# P-MT3620RDB-1-7_Dev.net
KiCad netlist of a schematic drawn in Altium Designer
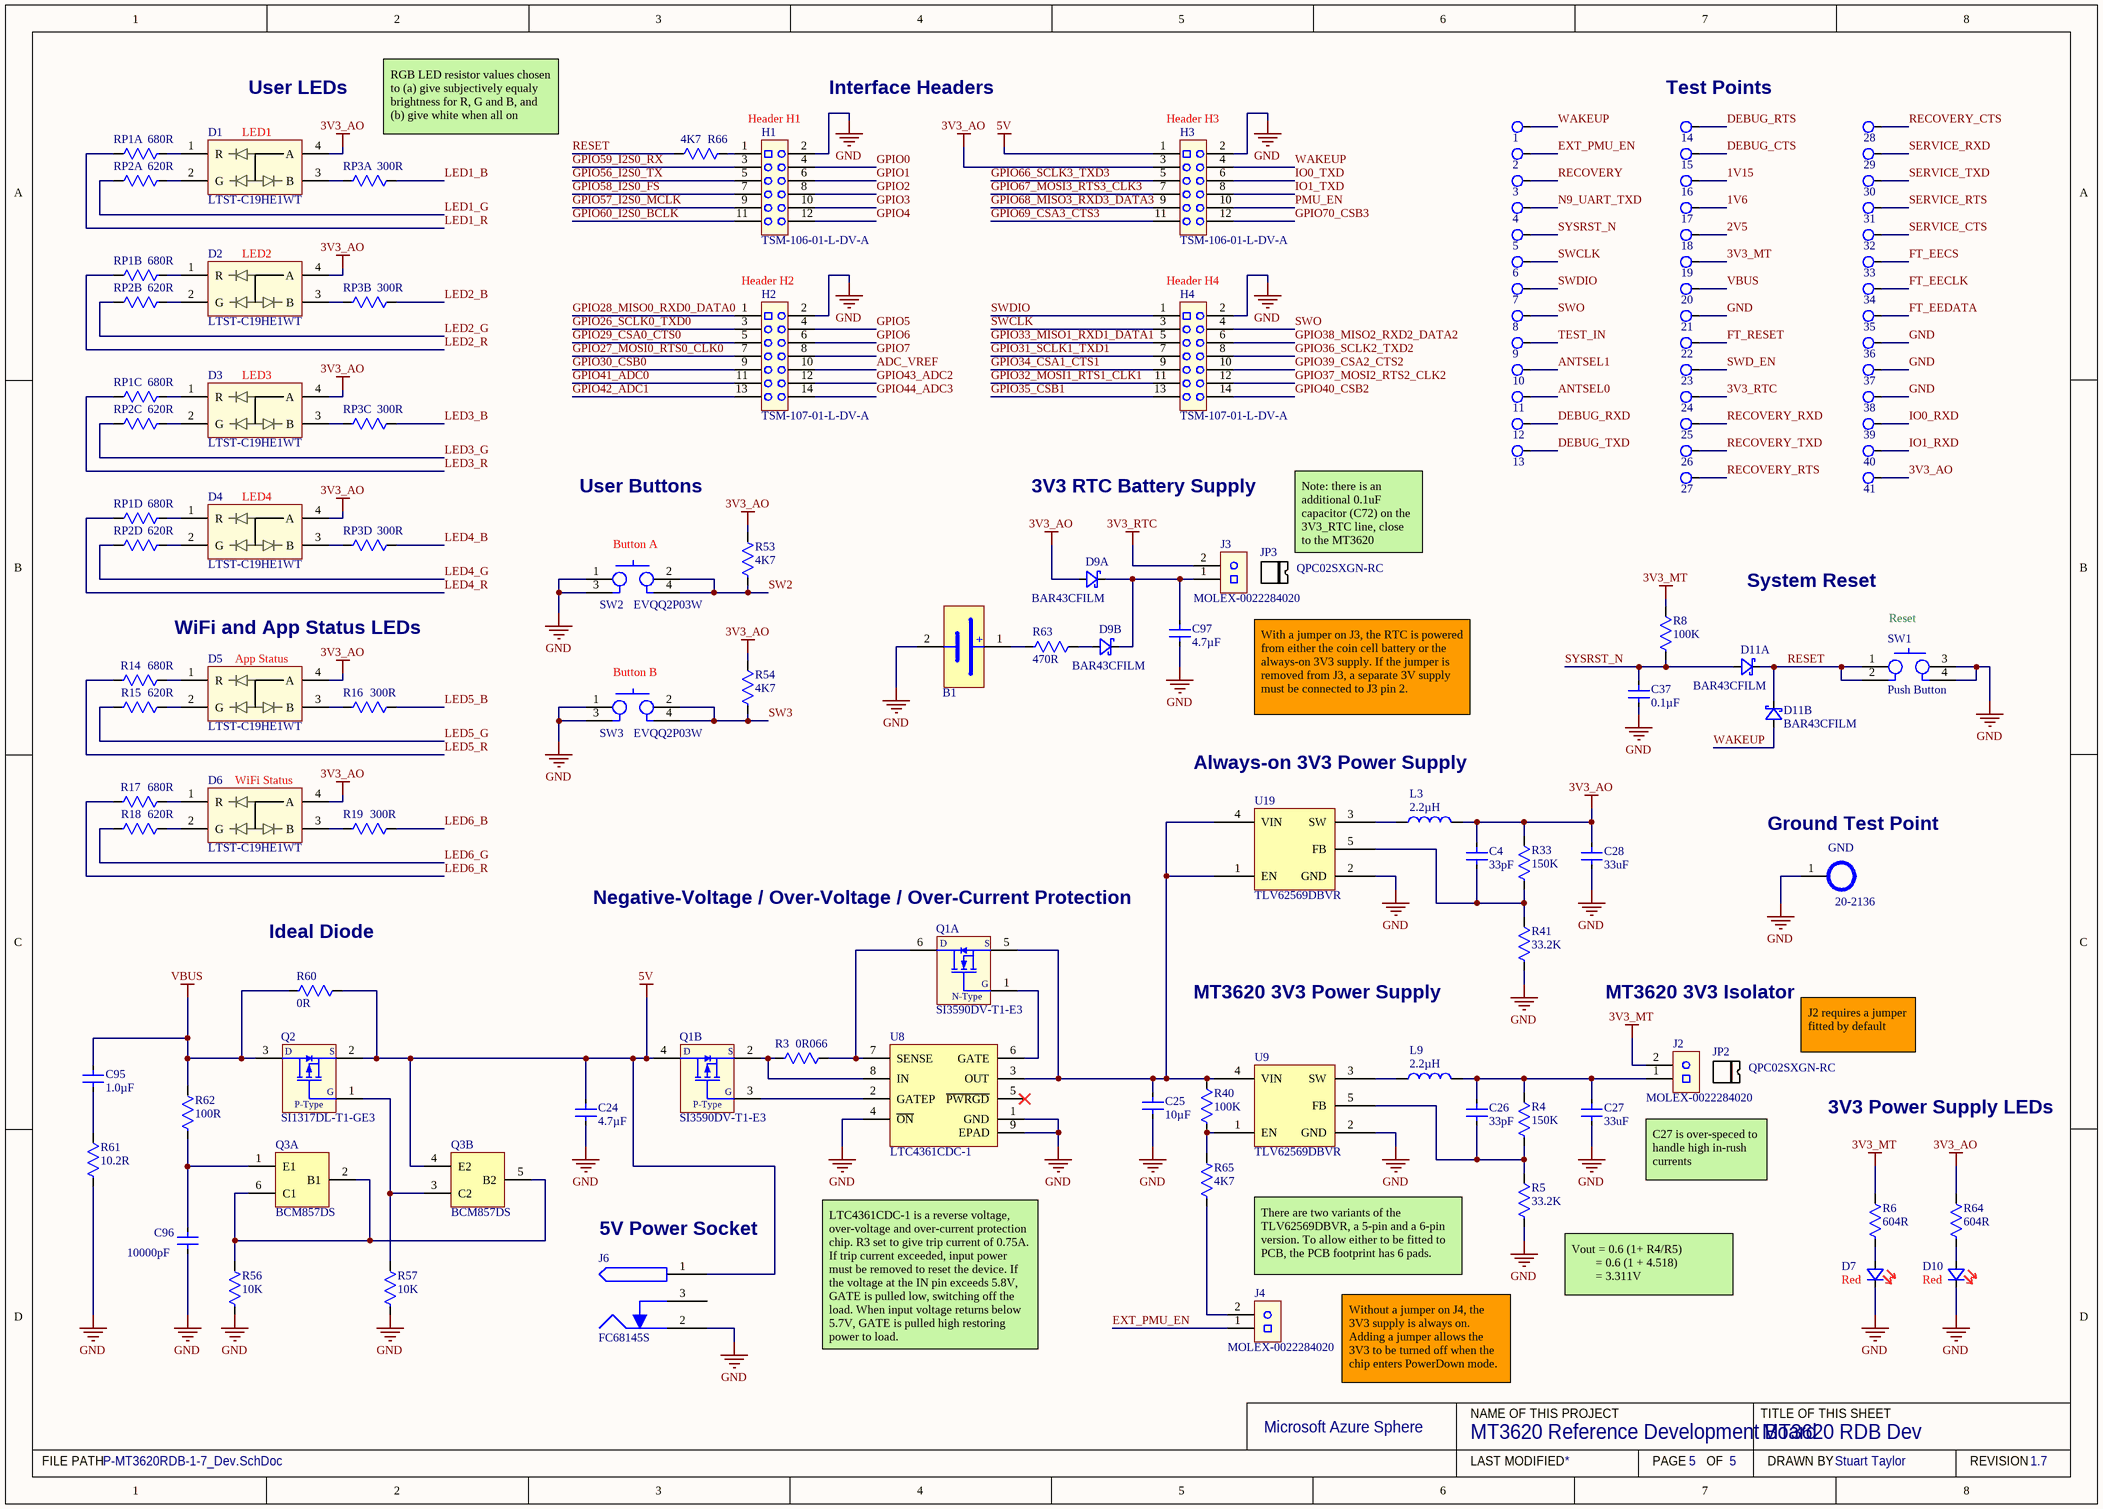
[diagram p0: P-MT3620RDB-1-7_Dev.SchDoc]

(export (version "E")
  (design (tool "Eeschema 10.0.6"))
  (components
    (comp (ref "1")
      (value "TestPoint")
      (footprint "Pad1.27mm")
      (description "Test Point")
      (libsource (lib "generic") (part "TestPoint"))
    )
    (comp (ref "2")
      (value "TestPoint")
      (footprint "Pad1.27mm")
      (description "Test Point")
      (libsource (lib "generic") (part "TestPoint"))
    )
    (comp (ref "3")
      (value "TestPoint")
      (footprint "Pad1.27mm")
      (description "Test Point")
      (libsource (lib "generic") (part "TestPoint"))
    )
    (comp (ref "4")
      (value "TestPoint")
      (footprint "Pad1.27mm")
      (description "Test Point")
      (libsource (lib "generic") (part "TestPoint"))
    )
    (comp (ref "5")
      (value "TestPoint")
      (footprint "Pad1.27mm")
      (description "Test Point")
      (libsource (lib "generic") (part "TestPoint"))
    )
    (comp (ref "6")
      (value "TestPoint")
      (footprint "Pad1.27mm")
      (description "Test Point")
      (libsource (lib "generic") (part "TestPoint"))
    )
    (comp (ref "7")
      (value "TestPoint")
      (footprint "Pad1.27mm")
      (description "Test Point")
      (libsource (lib "generic") (part "TestPoint"))
    )
    (comp (ref "8")
      (value "TestPoint")
      (footprint "Pad1.27mm")
      (description "Test Point")
      (libsource (lib "generic") (part "TestPoint"))
    )
    (comp (ref "9")
      (value "TestPoint")
      (footprint "Pad1.27mm")
      (description "Test Point")
      (libsource (lib "generic") (part "TestPoint"))
    )
    (comp (ref "10")
      (value "TestPoint")
      (footprint "Pad1.27mm")
      (description "Test Point")
      (libsource (lib "generic") (part "TestPoint"))
    )
    (comp (ref "11")
      (value "TestPoint")
      (footprint "Pad1.27mm")
      (description "Test Point")
      (libsource (lib "generic") (part "TestPoint"))
    )
    (comp (ref "12")
      (value "TestPoint")
      (footprint "Pad1.27mm")
      (description "Test Point")
      (libsource (lib "generic") (part "TestPoint"))
    )
    (comp (ref "13")
      (value "TestPoint")
      (footprint "Pad1.27mm")
      (description "Test Point")
      (libsource (lib "generic") (part "TestPoint"))
    )
    (comp (ref "14")
      (value "TestPoint")
      (footprint "Pad1.27mm")
      (description "Test Point")
      (libsource (lib "generic") (part "TestPoint"))
    )
    (comp (ref "15")
      (value "TestPoint")
      (footprint "Pad1.27mm")
      (description "Test Point")
      (libsource (lib "generic") (part "TestPoint"))
    )
    (comp (ref "16")
      (value "TestPoint")
      (footprint "Pad1.27mm")
      (description "Test Point")
      (libsource (lib "generic") (part "TestPoint"))
    )
    (comp (ref "17")
      (value "TestPoint")
      (footprint "Pad1.27mm")
      (description "Test Point")
      (libsource (lib "generic") (part "TestPoint"))
    )
    (comp (ref "18")
      (value "TestPoint")
      (footprint "Pad1.27mm")
      (description "Test Point")
      (libsource (lib "generic") (part "TestPoint"))
    )
    (comp (ref "19")
      (value "TestPoint")
      (footprint "Pad1.27mm")
      (description "Test Point")
      (libsource (lib "generic") (part "TestPoint"))
    )
    (comp (ref "20")
      (value "TestPoint")
      (footprint "Pad1.27mm")
      (description "Test Point")
      (libsource (lib "generic") (part "TestPoint"))
    )
    (comp (ref "21")
      (value "TestPoint")
      (footprint "Pad1.27mm")
      (description "Test Point")
      (libsource (lib "generic") (part "TestPoint"))
    )
    (comp (ref "22")
      (value "TestPoint")
      (footprint "Pad1.27mm")
      (description "Test Point")
      (libsource (lib "generic") (part "TestPoint"))
    )
    (comp (ref "23")
      (value "TestPoint")
      (footprint "Pad1.27mm")
      (description "Test Point")
      (libsource (lib "generic") (part "TestPoint"))
    )
    (comp (ref "24")
      (value "TestPoint")
      (footprint "Pad1.27mm")
      (description "Test Point")
      (libsource (lib "generic") (part "TestPoint"))
    )
    (comp (ref "25")
      (value "TestPoint")
      (footprint "Pad1.27mm")
      (description "Test Point")
      (libsource (lib "generic") (part "TestPoint"))
    )
    (comp (ref "26")
      (value "TestPoint")
      (footprint "Pad1.27mm")
      (description "Test Point")
      (libsource (lib "generic") (part "TestPoint"))
    )
    (comp (ref "27")
      (value "TestPoint")
      (footprint "Pad1.27mm")
      (description "Test Point")
      (libsource (lib "generic") (part "TestPoint"))
    )
    (comp (ref "28")
      (value "TestPoint")
      (footprint "Pad1.27mm")
      (description "Test Point")
      (libsource (lib "generic") (part "TestPoint"))
    )
    (comp (ref "29")
      (value "TestPoint")
      (footprint "Pad1.27mm")
      (description "Test Point")
      (libsource (lib "generic") (part "TestPoint"))
    )
    (comp (ref "30")
      (value "TestPoint")
      (footprint "Pad1.27mm")
      (description "Test Point")
      (libsource (lib "generic") (part "TestPoint"))
    )
    (comp (ref "31")
      (value "TestPoint")
      (footprint "Pad1.27mm")
      (description "Test Point")
      (libsource (lib "generic") (part "TestPoint"))
    )
    (comp (ref "32")
      (value "TestPoint")
      (footprint "Pad1.27mm")
      (description "Test Point")
      (libsource (lib "generic") (part "TestPoint"))
    )
    (comp (ref "33")
      (value "TestPoint")
      (footprint "Pad1.27mm")
      (description "Test Point")
      (libsource (lib "generic") (part "TestPoint"))
    )
    (comp (ref "34")
      (value "TestPoint")
      (footprint "Pad1.27mm")
      (description "Test Point")
      (libsource (lib "generic") (part "TestPoint"))
    )
    (comp (ref "35")
      (value "TestPoint")
      (footprint "Pad1.27mm")
      (description "Test Point")
      (libsource (lib "generic") (part "TestPoint"))
    )
    (comp (ref "36")
      (value "TestPoint")
      (footprint "Pad1.27mm")
      (description "Test Point")
      (libsource (lib "generic") (part "TestPoint"))
    )
    (comp (ref "37")
      (value "TestPoint")
      (footprint "Pad1.27mm")
      (description "Test Point")
      (libsource (lib "generic") (part "TestPoint"))
    )
    (comp (ref "38")
      (value "TestPoint")
      (footprint "Pad1.27mm")
      (description "Test Point")
      (libsource (lib "generic") (part "TestPoint"))
    )
    (comp (ref "39")
      (value "TestPoint")
      (footprint "Pad1.27mm")
      (description "Test Point")
      (libsource (lib "generic") (part "TestPoint"))
    )
    (comp (ref "40")
      (value "TestPoint")
      (footprint "Pad1.27mm")
      (description "Test Point")
      (libsource (lib "generic") (part "TestPoint"))
    )
    (comp (ref "41")
      (value "TestPoint")
      (footprint "Pad1.27mm")
      (description "Test Point")
      (libsource (lib "generic") (part "TestPoint"))
    )
    (comp (ref "B1")
      (value "HARWIN-S8421-45R")
      (footprint "HARWIN-S8421-45R")
      (description "SMT CR2032 coin cell holder")
      (fields (field (name "MANUFACTURER") "HARWIN") (field (name "MANUFACTURER PART NUMBER") "S8421-45R"))
      (libsource (lib "Harwin") (part "HARWIN-S8421-45R"))
    )
    (comp (ref "C4")
      (value "33pF")
      (footprint "CAPC1005-EIA0402 0.55MM MED")
      (description "CAP CER 33PF 50V 5% NP0 0402")
      (fields
        (field (name "MANUFACTURER") "TDK Corporation")
        (field (name "MANUFACTURER PART NUMBER") "C1005C0G1H330J050BA")
        (field (name "CAPACITANCE") "33pF")
      )
      (libsource (lib "TDK_Capacitor_C_0402") (part "33pF 0402 C0G, NP0 50V"))
    )
    (comp (ref "C24")
      (value "4.7µF")
      (footprint "CAPC1005-EIA0402 0.55MM MED")
      (description "CAP CER 4.7UF 10V 10% X5R 0402")
      (fields
        (field (name "MANUFACTURER") "TDK Corporation")
        (field (name "MANUFACTURER PART NUMBER") "C1005X5R1A475K050BC")
        (field (name "CAPACITANCE") "4.7µF")
      )
      (libsource (lib "TDK_Capacitor_C_0402") (part "4.7µF 0402 X5R 10V"))
    )
    (comp (ref "C25")
      (value "10µF")
      (footprint "CAPC1608-EIA0603-1MM-MED")
      (description "CAP CER 10UF 25V 20% X5R 0603")
      (fields
        (field (name "MANUFACTURER") "TDK Corporation")
        (field (name "MANUFACTURER PART NUMBER") "C1608X5R1E106M080AC")
        (field (name "CAPACITANCE") "10µF")
      )
      (libsource (lib "TDK-Capacitor_C_0603") (part "10µF 0603 X5R 25V"))
    )
    (comp (ref "C26")
      (value "33pF")
      (footprint "CAPC1005-EIA0402 0.55MM MED")
      (description "CAP CER 33PF 50V 5% NP0 0402")
      (fields
        (field (name "MANUFACTURER") "TDK Corporation")
        (field (name "MANUFACTURER PART NUMBER") "C1005C0G1H330J050BA")
        (field (name "CAPACITANCE") "33pF")
      )
      (libsource (lib "TDK_Capacitor_C_0402") (part "33pF 0402 C0G, NP0 50V"))
    )
    (comp (ref "C27")
      (value "33uF")
      (footprint "TDK_0805")
      (description "CAP CER 33UF 6.3V X5R 0805")
      (fields
        (field (name "MANUFACTURER") "TDK")
        (field (name "MANUFACTURER PART NUMBER") "C2012X5R0J336M125AC")
      )
      (libsource (lib "TDK_Capacitor_C_0805") (part "33uF 0805 X5R 6.3V"))
    )
    (comp (ref "C28")
      (value "33uF")
      (footprint "TDK_0805")
      (description "CAP CER 33UF 6.3V X5R 0805")
      (fields
        (field (name "MANUFACTURER") "TDK")
        (field (name "MANUFACTURER PART NUMBER") "C2012X5R0J336M125AC")
      )
      (libsource (lib "TDK_Capacitor_C_0805") (part "33uF 0805 X5R 6.3V"))
    )
    (comp (ref "C37")
      (value "0.1µF")
      (footprint "CAPC1005-EIA0402 0.55MM MED")
      (description "CAP CER 0.1UF 50V 10% X7R 0402")
      (fields
        (field (name "MANUFACTURER") "TDK Corporation")
        (field (name "MANUFACTURER PART NUMBER") "C1005X7R1H104K050BB")
        (field (name "CAPACITANCE") "0.1µF")
      )
      (libsource (lib "TDK_Capacitor_C_0402") (part "0.1µF 0402 X7R 50V"))
    )
    (comp (ref "C95")
      (value "1.0µF")
      (footprint "CAPC1005-EIA0402 0.55MM MED")
      (description "CAP CER 1UF 35V 10% X5R 0402")
      (fields
        (field (name "MANUFACTURER") "TDK Corporation")
        (field (name "MANUFACTURER PART NUMBER") "C1005X5R1V105K050BC")
        (field (name "CAPACITANCE") "1.0µF")
      )
      (libsource (lib "TDK_Capacitor_C_0402") (part "1.0µF 0402 X5R 35V"))
    )
    (comp (ref "C96")
      (value "10000pF")
      (footprint "CAPC1005-EIA0402 0.55MM MED")
      (description "CAP CER 10000PF 50V 10% X7R 0402")
      (fields
        (field (name "MANUFACTURER") "TDK Corporation")
        (field (name "MANUFACTURER PART NUMBER") "C1005X7R1H103K050BB")
        (field (name "CAPACITANCE") "10000pF")
      )
      (libsource (lib "TDK_Capacitor_C_0402") (part "10000pF 0402 X7R 50V"))
    )
    (comp (ref "C97")
      (value "4.7µF")
      (footprint "CAPC1005-EIA0402 0.55MM MED")
      (description "CAP CER 4.7UF 10V 10% X5R 0402")
      (fields
        (field (name "MANUFACTURER") "TDK Corporation")
        (field (name "MANUFACTURER PART NUMBER") "C1005X5R1A475K050BC")
        (field (name "CAPACITANCE") "4.7µF")
      )
      (libsource (lib "TDK_Capacitor_C_0402") (part "4.7µF 0402 X5R 10V"))
    )
    (comp (ref "D1")
      (value "LTST-C19HE1WT")
      (footprint "LTST-C19HE1WT")
      (description "LED RGB DIFFUSED 0606 SMD")
      (fields (field (name "MANUFACTURER") "Lite-On Inc."))
      (libsource (lib "Lite-On") (part "LTST-C19HE1WT"))
    )
    (comp (ref "D2")
      (value "LTST-C19HE1WT")
      (footprint "LTST-C19HE1WT")
      (description "LED RGB DIFFUSED 0606 SMD")
      (fields (field (name "MANUFACTURER") "Lite-On Inc."))
      (libsource (lib "Lite-On") (part "LTST-C19HE1WT"))
    )
    (comp (ref "D3")
      (value "LTST-C19HE1WT")
      (footprint "LTST-C19HE1WT")
      (description "LED RGB DIFFUSED 0606 SMD")
      (fields (field (name "MANUFACTURER") "Lite-On Inc."))
      (libsource (lib "Lite-On") (part "LTST-C19HE1WT"))
    )
    (comp (ref "D4")
      (value "LTST-C19HE1WT")
      (footprint "LTST-C19HE1WT")
      (description "LED RGB DIFFUSED 0606 SMD")
      (fields (field (name "MANUFACTURER") "Lite-On Inc."))
      (libsource (lib "Lite-On") (part "LTST-C19HE1WT"))
    )
    (comp (ref "D5")
      (value "LTST-C19HE1WT")
      (footprint "LTST-C19HE1WT")
      (description "LED RGB DIFFUSED 0606 SMD")
      (fields (field (name "MANUFACTURER") "Lite-On Inc."))
      (libsource (lib "Lite-On") (part "LTST-C19HE1WT"))
    )
    (comp (ref "D6")
      (value "LTST-C19HE1WT")
      (footprint "LTST-C19HE1WT")
      (description "LED RGB DIFFUSED 0606 SMD")
      (fields (field (name "MANUFACTURER") "Lite-On Inc."))
      (libsource (lib "Lite-On") (part "LTST-C19HE1WT"))
    )
    (comp (ref "D7")
      (value "Red LED")
      (footprint "Rohm SML-D12 Red")
      (description "1.6 x 0.8 x 0.55mm (0603) LED 620nm Red")
      (fields
        (field (name "MANUFACTURER") "Rohm Semiconductor")
        (field (name "MANUFACTURER PART NUMBER") "SML-D12U8WT86")
        (field (name "COLOUR") "Red")
      )
      (libsource (lib "Rohm") (part "SML-D12U"))
    )
    (comp (ref "D9")
      (value "BAR43CFILM")
      (footprint "ON_SEMI-SOT23-3")
      (description "DIODE ARRAY SCHOTTKY 30V SOT23-3")
      (fields (field (name "MANUFACTURER") "STMicroelectronics"))
      (libsource (lib "ST") (part "BAR43CFILM"))
    )
    (comp (ref "D10")
      (value "Red LED")
      (footprint "Rohm SML-D12 Red")
      (description "1.6 x 0.8 x 0.55mm (0603) LED 620nm Red")
      (fields
        (field (name "MANUFACTURER") "Rohm Semiconductor")
        (field (name "MANUFACTURER PART NUMBER") "SML-D12U8WT86")
        (field (name "COLOUR") "Red")
      )
      (libsource (lib "Rohm") (part "SML-D12U"))
    )
    (comp (ref "D11")
      (value "BAR43CFILM")
      (footprint "ON_SEMI-SOT23-3")
      (description "DIODE ARRAY SCHOTTKY 30V SOT23-3")
      (fields (field (name "MANUFACTURER") "STMicroelectronics"))
      (libsource (lib "ST") (part "BAR43CFILM"))
    )
    (comp (ref "GND")
      (value "20-2136")
      (footprint "20-2136")
      (description "VERO - 20-2136 - TERMINAL, PCB, BLACK, PK100")
      (fields (field (name "MANUFACTURER") "VERO"))
      (libsource (lib "Vero") (part "20-2136"))
    )
    (comp (ref "H1")
      (value "TSM-106-01-L-DV-A")
      (footprint "TSM-106-01-L-DV-A")
      (description "CONN HEADER 12POS .100\" SMD GOLD")
      (fields (field (name "MANUFACTURER") "Samtec"))
      (libsource (lib "Samtec") (part "TSM-106-01-L-DV-A"))
    )
    (comp (ref "H2")
      (value "TSM-107-01-L-DV-A")
      (footprint "TSM-107-01-L-DV-A")
      (description "CONN HEADER 14POS .100\" SMD GOLD")
      (fields (field (name "MANUFACTURER") "Samtec"))
      (libsource (lib "Samtec") (part "TSM-107-01-L-DV-A"))
    )
    (comp (ref "H3")
      (value "TSM-106-01-L-DV-A")
      (footprint "TSM-106-01-L-DV-A")
      (description "CONN HEADER 12POS .100\" SMD GOLD")
      (fields (field (name "MANUFACTURER") "Samtec"))
      (libsource (lib "Samtec") (part "TSM-106-01-L-DV-A"))
    )
    (comp (ref "H4")
      (value "TSM-107-01-L-DV-A")
      (footprint "TSM-107-01-L-DV-A")
      (description "CONN HEADER 14POS .100\" SMD GOLD")
      (fields (field (name "MANUFACTURER") "Samtec"))
      (libsource (lib "Samtec") (part "TSM-107-01-L-DV-A"))
    )
    (comp (ref "J2")
      (value "MOLEX-0022284020")
      (footprint "0022284020")
      (description "CONN HEADER 2POS .100 VERT TIN")
      (fields
        (field (name "MANUFACTURER") "Molex, LLC")
        (field (name "MANUFACTURER PART NUMBER") "0022284020")
      )
      (libsource (lib "Molex") (part "MOLEX-0022284020"))
    )
    (comp (ref "J3")
      (value "MOLEX-0022284020")
      (footprint "0022284020")
      (description "CONN HEADER 2POS .100 VERT TIN")
      (fields
        (field (name "MANUFACTURER") "Molex, LLC")
        (field (name "MANUFACTURER PART NUMBER") "0022284020")
      )
      (libsource (lib "Molex") (part "MOLEX-0022284020"))
    )
    (comp (ref "J4")
      (value "MOLEX-0022284020")
      (footprint "0022284020")
      (description "CONN HEADER 2POS .100 VERT TIN")
      (fields
        (field (name "MANUFACTURER") "Molex, LLC")
        (field (name "MANUFACTURER PART NUMBER") "0022284020")
      )
      (libsource (lib "Molex") (part "MOLEX-0022284020"))
    )
    (comp (ref "J6")
      (value "FC68145S")
      (footprint "FC68145S")
      (description "CLIFF ELECTRONIC COMPONENTS, FC68145S, DC Power Connector, Jack, 1 A, 1.3 mm, Surface Mount")
      (fields (field (name "MANUFACTURER") "Cliff"))
      (libsource (lib "Cliff") (part "FC68145S"))
    )
    (comp (ref "JP2")
      (value "QPC02SXGN-RC")
      (description "CONN JUMPER SHORTING .100\" GOLD")
      (fields (field (name "MANUFACTURER") "Sullins"))
      (libsource (lib "SullinsConnectorSolutions") (part "QPC02SXGN-RC"))
    )
    (comp (ref "JP3")
      (value "QPC02SXGN-RC")
      (description "CONN JUMPER SHORTING .100\" GOLD")
      (fields (field (name "MANUFACTURER") "Sullins"))
      (libsource (lib "SullinsConnectorSolutions") (part "QPC02SXGN-RC"))
    )
    (comp (ref "L3")
      (value "2.2µH")
      (footprint "NR3015T2R2M")
      (description "FIXED IND 2.2UH 1.5A 72 MOHM SMD")
      (fields
        (field (name "MANUFACTURER") "Taiyo Yuden")
        (field (name "MANUFACTURER PART NUMBER") "NR3015T2R2M")
      )
      (libsource (lib "TaiyoYuden ") (part "NR3015T2R2M"))
    )
    (comp (ref "L9")
      (value "2.2µH")
      (footprint "NR3015T2R2M")
      (description "FIXED IND 2.2UH 1.5A 72 MOHM SMD")
      (fields
        (field (name "MANUFACTURER") "Taiyo Yuden")
        (field (name "MANUFACTURER PART NUMBER") "NR3015T2R2M")
      )
      (libsource (lib "TaiyoYuden ") (part "NR3015T2R2M"))
    )
    (comp (ref "Q1")
      (value "SI3590DV-T1-E3")
      (footprint "SI3590DV-T1-E3")
      (description "MOSFET N&P-CH 30V (D-S)")
      (fields (field (name "MANUFACTURER") "Vishay Siliconix"))
      (libsource (lib "Vishay") (part "SI3590DV-T1-E3"))
    )
    (comp (ref "Q2")
      (value "SI1317DL-T1-GE3")
      (footprint "VISHAY_SOT-323")
      (description "VISHAY SI1317DL-T1-GE3 MOSFET Transistor, P Channel, -1.4 A, -20 V, 0.125 ohm, -4.5 V, 450 mV")
      (fields (field (name "MANUFACTURER") "Vishay Siliconix"))
      (libsource (lib "Vishay") (part "SI1317DL-T1-GE3"))
    )
    (comp (ref "Q3")
      (value "BCM857DS")
      (footprint "NXP-SOT457")
      (description "BJT ARRAY, DUAL PNP, -45V, -100MA, 6-SOT-457")
      (fields
        (field (name "MANUFACTURER") "NXP Semiconductors")
        (field (name "MANUFACTURER PART NUMBER") "BCM857DS,115")
      )
      (libsource (lib "NXP") (part "BCM857DS,115"))
    )
    (comp (ref "R3")
      (value "0R066")
      (footprint "VISHAY-0603")
      (description "Current Sense Resistors - SMD .4watt .066ohm 1%")
      (fields
        (field (name "MANUFACTURER") "Vishay Dale")
        (field (name "MANUFACTURER PART NUMBER") "WSLP0603R0660FEB")
      )
      (libsource (lib "Vishay") (part "WSLP0603R0660FEB"))
    )
    (comp (ref "R4")
      (value "150K")
      (footprint "RES 0402 MEDIUM DENSITY")
      (description "RES 150K OHM 1/10W 1% 0402 SMD")
      (fields
        (field (name "MANUFACTURER") "Panasonic Electronic Components")
        (field (name "MANUFACTURER PART NUMBER") "ERJ-2RKF1503X")
        (field (name "RESISTANCE (OHMS)") "150K")
      )
      (libsource (lib "Panasonic_Resistor_ERJ2R") (part "150K"))
    )
    (comp (ref "R5")
      (value "33.2K")
      (footprint "RES 0402 MEDIUM DENSITY")
      (description "RES 33.2K OHM 1/10W 1% 0402 SMD")
      (fields
        (field (name "MANUFACTURER") "Panasonic Electronic Components")
        (field (name "MANUFACTURER PART NUMBER") "ERJ-2RKF3322X")
        (field (name "RESISTANCE (OHMS)") "33.2K")
      )
      (libsource (lib "Panasonic_Resistor_ERJ2R") (part "33.2K"))
    )
    (comp (ref "R6")
      (value "604R")
      (footprint "RES 0402 MEDIUM DENSITY")
      (description "RES 604 OHM 1/10W 1% 0402 SMD")
      (fields
        (field (name "MANUFACTURER") "Panasonic Electronic Components")
        (field (name "MANUFACTURER PART NUMBER") "ERJ-2RKF6040X")
        (field (name "RESISTANCE (OHMS)") "604R")
      )
      (libsource (lib "Panasonic_Resistor_ERJ2R") (part "604R"))
    )
    (comp (ref "R8")
      (value "100K")
      (footprint "RES 0402 MEDIUM DENSITY")
      (description "RES 100K OHM 1/10W 1% 0402 SMD")
      (fields
        (field (name "MANUFACTURER") "Panasonic Electronic Components")
        (field (name "MANUFACTURER PART NUMBER") "ERJ-2RKF1003X")
        (field (name "RESISTANCE (OHMS)") "100K")
      )
      (libsource (lib "Panasonic_Resistor_ERJ2R") (part "100K"))
    )
    (comp (ref "R14")
      (value "680R")
      (footprint "RES 0402 MEDIUM DENSITY")
      (description "RES 680 OHM 1/10W 1% 0402 SMD")
      (fields
        (field (name "MANUFACTURER") "Panasonic Electronic Components")
        (field (name "MANUFACTURER PART NUMBER") "ERJ-2RKF6800X")
        (field (name "RESISTANCE (OHMS)") "680R")
      )
      (libsource (lib "Panasonic_Resistor_ERJ2R") (part "680R"))
    )
    (comp (ref "R15")
      (value "620R")
      (footprint "RES 0402 MEDIUM DENSITY")
      (description "RES 620 OHM 1/10W 1% 0402 SMD")
      (fields
        (field (name "MANUFACTURER") "Panasonic Electronic Components")
        (field (name "MANUFACTURER PART NUMBER") "ERJ-2RKF6200X")
        (field (name "RESISTANCE (OHMS)") "620R")
      )
      (libsource (lib "Panasonic_Resistor_ERJ2R") (part "620R"))
    )
    (comp (ref "R16")
      (value "300R")
      (footprint "RES 0402 MEDIUM DENSITY")
      (description "RES 300 OHM 1/10W 1% 0402 SMD")
      (fields
        (field (name "MANUFACTURER") "Panasonic Electronic Components")
        (field (name "MANUFACTURER PART NUMBER") "ERJ-2RKF3000X")
        (field (name "RESISTANCE (OHMS)") "300R")
      )
      (libsource (lib "Panasonic_Resistor_ERJ2R") (part "300R"))
    )
    (comp (ref "R17")
      (value "680R")
      (footprint "RES 0402 MEDIUM DENSITY")
      (description "RES 680 OHM 1/10W 1% 0402 SMD")
      (fields
        (field (name "MANUFACTURER") "Panasonic Electronic Components")
        (field (name "MANUFACTURER PART NUMBER") "ERJ-2RKF6800X")
        (field (name "RESISTANCE (OHMS)") "680R")
      )
      (libsource (lib "Panasonic_Resistor_ERJ2R") (part "680R"))
    )
    (comp (ref "R18")
      (value "620R")
      (footprint "RES 0402 MEDIUM DENSITY")
      (description "RES 620 OHM 1/10W 1% 0402 SMD")
      (fields
        (field (name "MANUFACTURER") "Panasonic Electronic Components")
        (field (name "MANUFACTURER PART NUMBER") "ERJ-2RKF6200X")
        (field (name "RESISTANCE (OHMS)") "620R")
      )
      (libsource (lib "Panasonic_Resistor_ERJ2R") (part "620R"))
    )
    (comp (ref "R19")
      (value "300R")
      (footprint "RES 0402 MEDIUM DENSITY")
      (description "RES 300 OHM 1/10W 1% 0402 SMD")
      (fields
        (field (name "MANUFACTURER") "Panasonic Electronic Components")
        (field (name "MANUFACTURER PART NUMBER") "ERJ-2RKF3000X")
        (field (name "RESISTANCE (OHMS)") "300R")
      )
      (libsource (lib "Panasonic_Resistor_ERJ2R") (part "300R"))
    )
    (comp (ref "R33")
      (value "150K")
      (footprint "RES 0402 MEDIUM DENSITY")
      (description "RES 150K OHM 1/10W 1% 0402 SMD")
      (fields
        (field (name "MANUFACTURER") "Panasonic Electronic Components")
        (field (name "MANUFACTURER PART NUMBER") "ERJ-2RKF1503X")
        (field (name "RESISTANCE (OHMS)") "150K")
      )
      (libsource (lib "Panasonic_Resistor_ERJ2R") (part "150K"))
    )
    (comp (ref "R40")
      (value "100K")
      (footprint "RES 0402 MEDIUM DENSITY")
      (description "RES 100K OHM 1/10W 1% 0402 SMD")
      (fields
        (field (name "MANUFACTURER") "Panasonic Electronic Components")
        (field (name "MANUFACTURER PART NUMBER") "ERJ-2RKF1003X")
        (field (name "RESISTANCE (OHMS)") "100K")
      )
      (libsource (lib "Panasonic_Resistor_ERJ2R") (part "100K"))
    )
    (comp (ref "R41")
      (value "33.2K")
      (footprint "RES 0402 MEDIUM DENSITY")
      (description "RES 33.2K OHM 1/10W 1% 0402 SMD")
      (fields
        (field (name "MANUFACTURER") "Panasonic Electronic Components")
        (field (name "MANUFACTURER PART NUMBER") "ERJ-2RKF3322X")
        (field (name "RESISTANCE (OHMS)") "33.2K")
      )
      (libsource (lib "Panasonic_Resistor_ERJ2R") (part "33.2K"))
    )
    (comp (ref "R53")
      (value "4K7")
      (footprint "RES 0402 MEDIUM DENSITY")
      (description "RES 4.7K OHM 1/10W 1% 0402 SMD")
      (fields
        (field (name "MANUFACTURER") "Panasonic Electronic Components")
        (field (name "MANUFACTURER PART NUMBER") "ERJ-2RKF4701X")
        (field (name "RESISTANCE (OHMS)") "4K7")
      )
      (libsource (lib "Panasonic_Resistor_ERJ2R") (part "4.7K"))
    )
    (comp (ref "R54")
      (value "4K7")
      (footprint "RES 0402 MEDIUM DENSITY")
      (description "RES 4.7K OHM 1/10W 1% 0402 SMD")
      (fields
        (field (name "MANUFACTURER") "Panasonic Electronic Components")
        (field (name "MANUFACTURER PART NUMBER") "ERJ-2RKF4701X")
        (field (name "RESISTANCE (OHMS)") "4K7")
      )
      (libsource (lib "Panasonic_Resistor_ERJ2R") (part "4.7K"))
    )
    (comp (ref "R56")
      (value "10K")
      (footprint "RES 0402 MEDIUM DENSITY")
      (description "RES 10K OHM 1/10W 1% 0402 SMD")
      (fields
        (field (name "MANUFACTURER") "Panasonic Electronic Components")
        (field (name "MANUFACTURER PART NUMBER") "ERJ-2RKF1002X")
        (field (name "RESISTANCE (OHMS)") "10K")
      )
      (libsource (lib "Panasonic_Resistor_ERJ2R") (part "10K"))
    )
    (comp (ref "R57")
      (value "10K")
      (footprint "RES 0402 MEDIUM DENSITY")
      (description "RES 10K OHM 1/10W 1% 0402 SMD")
      (fields
        (field (name "MANUFACTURER") "Panasonic Electronic Components")
        (field (name "MANUFACTURER PART NUMBER") "ERJ-2RKF1002X")
        (field (name "RESISTANCE (OHMS)") "10K")
      )
      (libsource (lib "Panasonic_Resistor_ERJ2R") (part "10K"))
    )
    (comp (ref "R60")
      (value "0R")
      (footprint "RES 0402 MEDIUM DENSITY")
      (description "RES 0.0 OHM 1/10W JUMP 0402 SMD")
      (fields
        (field (name "MANUFACTURER") "Panasonic Electronic Components")
        (field (name "MANUFACTURER PART NUMBER") "ERJ-2GE0R00X")
        (field (name "RESISTANCE (OHMS)") "0R")
      )
      (libsource (lib "Panasonic_Resistor_ERJ2R") (part "0R"))
    )
    (comp (ref "R61")
      (value "10.2R")
      (footprint "RES 0402 MEDIUM DENSITY")
      (description "RES 10.2 OHM 1/10W 1% 0402 SMD")
      (fields
        (field (name "MANUFACTURER") "Panasonic Electronic Components")
        (field (name "MANUFACTURER PART NUMBER") "ERJ-2RKF10R2X")
        (field (name "RESISTANCE (OHMS)") "10.2R")
      )
      (libsource (lib "Panasonic_Resistor_ERJ2R") (part "10.2R"))
    )
    (comp (ref "R62")
      (value "100R")
      (footprint "RES 0402 MEDIUM DENSITY")
      (description "RES 100 OHM 1/10W 1% 0402 SMD")
      (fields
        (field (name "MANUFACTURER") "Panasonic Electronic Components")
        (field (name "MANUFACTURER PART NUMBER") "ERJ-2RKF1000X")
        (field (name "RESISTANCE (OHMS)") "100R")
      )
      (libsource (lib "Panasonic_Resistor_ERJ2R") (part "100R"))
    )
    (comp (ref "R63")
      (value "470R")
      (footprint "RES 0402 MEDIUM DENSITY")
      (description "RES 470 OHM 1/10W 1% 0402 SMD")
      (fields
        (field (name "MANUFACTURER") "Panasonic Electronic Components")
        (field (name "MANUFACTURER PART NUMBER") "ERJ-2RKF4700X")
        (field (name "RESISTANCE (OHMS)") "470R")
      )
      (libsource (lib "Panasonic_Resistor_ERJ2R") (part "470R"))
    )
    (comp (ref "R64")
      (value "604R")
      (footprint "RES 0402 MEDIUM DENSITY")
      (description "RES 604 OHM 1/10W 1% 0402 SMD")
      (fields
        (field (name "MANUFACTURER") "Panasonic Electronic Components")
        (field (name "MANUFACTURER PART NUMBER") "ERJ-2RKF6040X")
        (field (name "RESISTANCE (OHMS)") "604R")
      )
      (libsource (lib "Panasonic_Resistor_ERJ2R") (part "604R"))
    )
    (comp (ref "R65")
      (value "4K7")
      (footprint "RES 0402 MEDIUM DENSITY")
      (description "RES 4.7K OHM 1/10W 1% 0402 SMD")
      (fields
        (field (name "MANUFACTURER") "Panasonic Electronic Components")
        (field (name "MANUFACTURER PART NUMBER") "ERJ-2RKF4701X")
        (field (name "RESISTANCE (OHMS)") "4K7")
      )
      (libsource (lib "Panasonic_Resistor_ERJ2R") (part "4.7K"))
    )
    (comp (ref "R66")
      (value "4K7")
      (footprint "RES 0402 MEDIUM DENSITY")
      (description "RES 4.7K OHM 1/10W 1% 0402 SMD")
      (fields
        (field (name "MANUFACTURER") "Panasonic Electronic Components")
        (field (name "MANUFACTURER PART NUMBER") "ERJ-2RKF4701X")
        (field (name "RESISTANCE (OHMS)") "4K7")
      )
      (libsource (lib "Panasonic_Resistor_ERJ2R") (part "4.7K"))
    )
    (comp (ref "RP1")
      (value "680R")
      (footprint "EXB-N8V")
      (fields
        (field (name "MANUFACTURER") "Panasonic / Panasonic ECG")
        (field (name "MANUFACTURER PART NUMBER") "EXB-N8V681JX")
      )
      (libsource (lib "Panasonic") (part "EXB-N8V681JX"))
    )
    (comp (ref "RP2")
      (value "620R")
      (footprint "EXB-N8V")
      (fields
        (field (name "MANUFACTURER") "Panasonic ECG")
        (field (name "MANUFACTURER PART NUMBER") "EXB-N8V621JX")
        (field (name "TOLERANCE") "5%")
      )
      (libsource (lib "Panasonic") (part "EXB-N8V621JX"))
    )
    (comp (ref "RP3")
      (value "300R")
      (footprint "EXB-N8V")
      (fields
        (field (name "MANUFACTURER") "Panasonic / Panasonic ECG")
        (field (name "MANUFACTURER PART NUMBER") "EXB-N8V301JX")
        (field (name "TOLERANCE") "5%")
      )
      (libsource (lib "Panasonic") (part "EXB-N8V301JX"))
    )
    (comp (ref "SW1")
      (value "Push Button")
      (footprint "DHT-1158")
      (libsource (lib "Seeed") (part "DHT-1158"))
    )
    (comp (ref "SW2")
      (value "SWI TACT SPN0 PANASONIC EVQQ2P03W")
      (footprint "EVQQ2P03W")
      (description "PANASONIC - EVQQ2P03W - SWITCH, SPNO, SMD")
      (fields (field (name "MANUFACTURER") "PANASONIC") (field (name "MANUFACTURER PART NUMBER") "EVQQ2P03W"))
      (libsource (lib "switch") (part "SWI TACT SPN0 PANASONIC EVQQ2P03W"))
    )
    (comp (ref "SW3")
      (value "SWI TACT SPN0 PANASONIC EVQQ2P03W")
      (footprint "EVQQ2P03W")
      (description "PANASONIC - EVQQ2P03W - SWITCH, SPNO, SMD")
      (fields (field (name "MANUFACTURER") "PANASONIC") (field (name "MANUFACTURER PART NUMBER") "EVQQ2P03W"))
      (libsource (lib "switch") (part "SWI TACT SPN0 PANASONIC EVQQ2P03W"))
    )
    (comp (ref "U8")
      (value "LTC4361CDC-1")
      (footprint "LTC4361-1#TRPBF")
      (description "LINEAR TECHNOLOGY LTC4361CDC-1#TRMPBF IC, OVERVOLTAGE/CUR PROT, 8DFN")
      (fields
        (field (name "MANUFACTURER") "Linear Technology")
        (field (name "MANUFACTURER PART NUMBER") "LTC4361CDC-1#TRMPBF")
      )
      (libsource (lib "LinearTech") (part "LTC4361CDC-1#TRMPBF"))
    )
    (comp (ref "U9")
      (value "TLV62569DBVR")
      (footprint "TI-SOT23-6")
      (description "Variable voltage buck converter")
      (fields (field (name "MANUFACTURER") "Texas Instruments"))
      (libsource (lib "TexasInstruments") (part "TLV62569DBVR"))
    )
    (comp (ref "U19")
      (value "TLV62569DBVR")
      (footprint "TI-SOT23-6")
      (description "Variable voltage buck converter")
      (fields (field (name "MANUFACTURER") "Texas Instruments"))
      (libsource (lib "TexasInstruments") (part "TLV62569DBVR"))
    )
  )
  (nets
    (net (code "1") (name "/1V6") (class "Default")
      (node (ref "17") (pin "1") (pinfunction "1_1") (pintype "passive"))
    )
    (net (code "2") (name "/1V15") (class "Default")
      (node (ref "16") (pin "1") (pinfunction "1_1") (pintype "passive"))
    )
    (net (code "3") (name "/2V5") (class "Default")
      (node (ref "18") (pin "1") (pinfunction "1_1") (pintype "passive"))
    )
    (net (code "4") (name "/ADC_VREF") (class "Default")
      (node (ref "H2") (pin "10") (pinfunction "10_10") (pintype "passive"))
    )
    (net (code "5") (name "/ANTSEL0") (class "Default")
      (node (ref "11") (pin "1") (pinfunction "1_1") (pintype "passive"))
    )
    (net (code "6") (name "/ANTSEL1") (class "Default")
      (node (ref "10") (pin "1") (pinfunction "1_1") (pintype "passive"))
    )
    (net (code "7") (name "/DEBUG_CTS") (class "Default")
      (node (ref "15") (pin "1") (pinfunction "1_1") (pintype "passive"))
    )
    (net (code "8") (name "/DEBUG_RTS") (class "Default")
      (node (ref "14") (pin "1") (pinfunction "1_1") (pintype "passive"))
    )
    (net (code "9") (name "/DEBUG_RXD") (class "Default")
      (node (ref "12") (pin "1") (pinfunction "1_1") (pintype "passive"))
    )
    (net (code "10") (name "/DEBUG_TXD") (class "Default")
      (node (ref "13") (pin "1") (pinfunction "1_1") (pintype "passive"))
    )
    (net (code "11") (name "/EXT_PMU_EN") (class "Default")
      (node (ref "2") (pin "1") (pinfunction "1_1") (pintype "passive"))
      (node (ref "J4") (pin "1") (pinfunction "1_1") (pintype "passive"))
    )
    (net (code "12") (name "/FT_EECLK") (class "Default")
      (node (ref "34") (pin "1") (pinfunction "1_1") (pintype "passive"))
    )
    (net (code "13") (name "/FT_EECS") (class "Default")
      (node (ref "33") (pin "1") (pinfunction "1_1") (pintype "passive"))
    )
    (net (code "14") (name "/FT_EEDATA") (class "Default")
      (node (ref "35") (pin "1") (pinfunction "1_1") (pintype "passive"))
    )
    (net (code "15") (name "/FT_RESET") (class "Default")
      (node (ref "22") (pin "1") (pinfunction "1_1") (pintype "passive"))
    )
    (net (code "16") (name "/GPIO0") (class "Default")
      (node (ref "H1") (pin "4") (pinfunction "4_4") (pintype "passive"))
    )
    (net (code "17") (name "/GPIO1") (class "Default")
      (node (ref "H1") (pin "6") (pinfunction "6_6") (pintype "passive"))
    )
    (net (code "18") (name "/GPIO2") (class "Default")
      (node (ref "H1") (pin "8") (pinfunction "8_8") (pintype "passive"))
    )
    (net (code "19") (name "/GPIO3") (class "Default")
      (node (ref "H1") (pin "10") (pinfunction "10_10") (pintype "passive"))
    )
    (net (code "20") (name "/GPIO4") (class "Default")
      (node (ref "H1") (pin "12") (pinfunction "12_12") (pintype "passive"))
    )
    (net (code "21") (name "/GPIO5") (class "Default")
      (node (ref "H2") (pin "4") (pinfunction "4_4") (pintype "passive"))
    )
    (net (code "22") (name "/GPIO6") (class "Default")
      (node (ref "H2") (pin "6") (pinfunction "6_6") (pintype "passive"))
    )
    (net (code "23") (name "/GPIO7") (class "Default")
      (node (ref "H2") (pin "8") (pinfunction "8_8") (pintype "passive"))
    )
    (net (code "24") (name "/GPIO26_SCLK0_TXD0") (class "Default")
      (node (ref "H2") (pin "3") (pinfunction "3_3") (pintype "passive"))
    )
    (net (code "25") (name "/GPIO27_MOSI0_RTS0_CLK0") (class "Default")
      (node (ref "H2") (pin "7") (pinfunction "7_7") (pintype "passive"))
    )
    (net (code "26") (name "/GPIO28_MISO0_RXD0_DATA0") (class "Default")
      (node (ref "H2") (pin "1") (pinfunction "1_1") (pintype "passive"))
    )
    (net (code "27") (name "/GPIO29_CSA0_CTS0") (class "Default")
      (node (ref "H2") (pin "5") (pinfunction "5_5") (pintype "passive"))
    )
    (net (code "28") (name "/GPIO30_CSB0") (class "Default")
      (node (ref "H2") (pin "9") (pinfunction "9_9") (pintype "passive"))
    )
    (net (code "29") (name "/GPIO31_SCLK1_TXD1") (class "Default")
      (node (ref "H4") (pin "7") (pinfunction "7_7") (pintype "passive"))
    )
    (net (code "30") (name "/GPIO32_MOSI1_RTS1_CLK1") (class "Default")
      (node (ref "H4") (pin "11") (pinfunction "11_11") (pintype "passive"))
    )
    (net (code "31") (name "/GPIO33_MISO1_RXD1_DATA1") (class "Default")
      (node (ref "H4") (pin "5") (pinfunction "5_5") (pintype "passive"))
    )
    (net (code "32") (name "/GPIO34_CSA1_CTS1") (class "Default")
      (node (ref "H4") (pin "9") (pinfunction "9_9") (pintype "passive"))
    )
    (net (code "33") (name "/GPIO35_CSB1") (class "Default")
      (node (ref "H4") (pin "13") (pinfunction "13_13") (pintype "passive"))
    )
    (net (code "34") (name "/GPIO36_SCLK2_TXD2") (class "Default")
      (node (ref "H4") (pin "8") (pinfunction "8_8") (pintype "passive"))
    )
    (net (code "35") (name "/GPIO37_MOSI2_RTS2_CLK2") (class "Default")
      (node (ref "H4") (pin "12") (pinfunction "12_12") (pintype "passive"))
    )
    (net (code "36") (name "/GPIO38_MISO2_RXD2_DATA2") (class "Default")
      (node (ref "H4") (pin "6") (pinfunction "6_6") (pintype "passive"))
    )
    (net (code "37") (name "/GPIO39_CSA2_CTS2") (class "Default")
      (node (ref "H4") (pin "10") (pinfunction "10_10") (pintype "passive"))
    )
    (net (code "38") (name "/GPIO40_CSB2") (class "Default")
      (node (ref "H4") (pin "14") (pinfunction "14_14") (pintype "passive"))
    )
    (net (code "39") (name "/GPIO41_ADC0") (class "Default")
      (node (ref "H2") (pin "11") (pinfunction "11_11") (pintype "passive"))
    )
    (net (code "40") (name "/GPIO42_ADC1") (class "Default")
      (node (ref "H2") (pin "13") (pinfunction "13_13") (pintype "passive"))
    )
    (net (code "41") (name "/GPIO43_ADC2") (class "Default")
      (node (ref "H2") (pin "12") (pinfunction "12_12") (pintype "passive"))
    )
    (net (code "42") (name "/GPIO44_ADC3") (class "Default")
      (node (ref "H2") (pin "14") (pinfunction "14_14") (pintype "passive"))
    )
    (net (code "43") (name "/GPIO56_I2S0_TX") (class "Default")
      (node (ref "H1") (pin "5") (pinfunction "5_5") (pintype "passive"))
    )
    (net (code "44") (name "/GPIO57_I2S0_MCLK") (class "Default")
      (node (ref "H1") (pin "9") (pinfunction "9_9") (pintype "passive"))
    )
    (net (code "45") (name "/GPIO58_I2S0_FS") (class "Default")
      (node (ref "H1") (pin "7") (pinfunction "7_7") (pintype "passive"))
    )
    (net (code "46") (name "/GPIO59_I2S0_RX") (class "Default")
      (node (ref "H1") (pin "3") (pinfunction "3_3") (pintype "passive"))
    )
    (net (code "47") (name "/GPIO60_I2S0_BCLK") (class "Default")
      (node (ref "H1") (pin "11") (pinfunction "11_11") (pintype "passive"))
    )
    (net (code "48") (name "/GPIO66_SCLK3_TXD3") (class "Default")
      (node (ref "H3") (pin "5") (pinfunction "5_5") (pintype "passive"))
    )
    (net (code "49") (name "/GPIO67_MOSI3_RTS3_CLK3") (class "Default")
      (node (ref "H3") (pin "7") (pinfunction "7_7") (pintype "passive"))
    )
    (net (code "50") (name "/GPIO68_MISO3_RXD3_DATA3") (class "Default")
      (node (ref "H3") (pin "9") (pinfunction "9_9") (pintype "passive"))
    )
    (net (code "51") (name "/GPIO69_CSA3_CTS3") (class "Default")
      (node (ref "H3") (pin "11") (pinfunction "11_11") (pintype "passive"))
    )
    (net (code "52") (name "/GPIO70_CSB3") (class "Default")
      (node (ref "H3") (pin "12") (pinfunction "12_12") (pintype "passive"))
    )
    (net (code "53") (name "/IO0_RXD") (class "Default")
      (node (ref "39") (pin "1") (pinfunction "1_1") (pintype "passive"))
    )
    (net (code "54") (name "/IO0_TXD") (class "Default")
      (node (ref "H3") (pin "6") (pinfunction "6_6") (pintype "passive"))
    )
    (net (code "55") (name "/IO1_RXD") (class "Default")
      (node (ref "40") (pin "1") (pinfunction "1_1") (pintype "passive"))
    )
    (net (code "56") (name "/IO1_TXD") (class "Default")
      (node (ref "H3") (pin "8") (pinfunction "8_8") (pintype "passive"))
    )
    (net (code "57") (name "/LED1_B") (class "Default")
      (node (ref "RP3") (pin "2") (pinfunction "2_2") (pintype "passive"))
    )
    (net (code "58") (name "/LED1_G") (class "Default")
      (node (ref "RP2") (pin "2") (pinfunction "2_2") (pintype "passive"))
    )
    (net (code "59") (name "/LED1_R") (class "Default")
      (node (ref "RP1") (pin "2") (pinfunction "2_2") (pintype "passive"))
    )
    (net (code "60") (name "/LED2_B") (class "Default")
      (node (ref "RP3") (pin "4") (pinfunction "4_4") (pintype "passive"))
    )
    (net (code "61") (name "/LED2_G") (class "Default")
      (node (ref "RP2") (pin "4") (pinfunction "4_4") (pintype "passive"))
    )
    (net (code "62") (name "/LED2_R") (class "Default")
      (node (ref "RP1") (pin "4") (pinfunction "4_4") (pintype "passive"))
    )
    (net (code "63") (name "/LED3_B") (class "Default")
      (node (ref "RP3") (pin "6") (pinfunction "6_6") (pintype "passive"))
    )
    (net (code "64") (name "/LED3_G") (class "Default")
      (node (ref "RP2") (pin "6") (pinfunction "6_6") (pintype "passive"))
    )
    (net (code "65") (name "/LED3_R") (class "Default")
      (node (ref "RP1") (pin "6") (pinfunction "6_6") (pintype "passive"))
    )
    (net (code "66") (name "/LED4_B") (class "Default")
      (node (ref "RP3") (pin "8") (pinfunction "8_8") (pintype "passive"))
    )
    (net (code "67") (name "/LED4_G") (class "Default")
      (node (ref "RP2") (pin "8") (pinfunction "8_8") (pintype "passive"))
    )
    (net (code "68") (name "/LED4_R") (class "Default")
      (node (ref "RP1") (pin "8") (pinfunction "8_8") (pintype "passive"))
    )
    (net (code "69") (name "/LED5_B") (class "Default")
      (node (ref "R16") (pin "1") (pinfunction "1_1") (pintype "passive"))
    )
    (net (code "70") (name "/LED5_G") (class "Default")
      (node (ref "R15") (pin "2") (pinfunction "2_2") (pintype "passive"))
    )
    (net (code "71") (name "/LED5_R") (class "Default")
      (node (ref "R14") (pin "2") (pinfunction "2_2") (pintype "passive"))
    )
    (net (code "72") (name "/LED6_B") (class "Default")
      (node (ref "R19") (pin "1") (pinfunction "1_1") (pintype "passive"))
    )
    (net (code "73") (name "/LED6_G") (class "Default")
      (node (ref "R18") (pin "2") (pinfunction "2_2") (pintype "passive"))
    )
    (net (code "74") (name "/LED6_R") (class "Default")
      (node (ref "R17") (pin "2") (pinfunction "2_2") (pintype "passive"))
    )
    (net (code "75") (name "/N9_UART_TXD") (class "Default")
      (node (ref "4") (pin "1") (pinfunction "1_1") (pintype "passive"))
    )
    (net (code "76") (name "/PMU_EN") (class "Default")
      (node (ref "H3") (pin "10") (pinfunction "10_10") (pintype "passive"))
    )
    (net (code "77") (name "/RECOVERY") (class "Default")
      (node (ref "3") (pin "1") (pinfunction "1_1") (pintype "passive"))
    )
    (net (code "78") (name "/RECOVERY_CTS") (class "Default")
      (node (ref "28") (pin "1") (pinfunction "1_1") (pintype "passive"))
    )
    (net (code "79") (name "/RECOVERY_RTS") (class "Default")
      (node (ref "27") (pin "1") (pinfunction "1_1") (pintype "passive"))
    )
    (net (code "80") (name "/RECOVERY_RXD") (class "Default")
      (node (ref "25") (pin "1") (pinfunction "1_1") (pintype "passive"))
    )
    (net (code "81") (name "/RECOVERY_TXD") (class "Default")
      (node (ref "26") (pin "1") (pinfunction "1_1") (pintype "passive"))
    )
    (net (code "82") (name "/RESET") (class "Default")
      (node (ref "D11") (pin "3") (pinfunction "K_3") (pintype "passive"))
      (node (ref "R66") (pin "1") (pinfunction "1_1") (pintype "passive"))
      (node (ref "SW1") (pin "1") (pinfunction "1_1") (pintype "passive"))
      (node (ref "SW1") (pin "2") (pinfunction "2_2") (pintype "passive"))
    )
    (net (code "83") (name "/SERVICE_CTS") (class "Default")
      (node (ref "32") (pin "1") (pinfunction "1_1") (pintype "passive"))
    )
    (net (code "84") (name "/SERVICE_RTS") (class "Default")
      (node (ref "31") (pin "1") (pinfunction "1_1") (pintype "passive"))
    )
    (net (code "85") (name "/SERVICE_RXD") (class "Default")
      (node (ref "29") (pin "1") (pinfunction "1_1") (pintype "passive"))
    )
    (net (code "86") (name "/SERVICE_TXD") (class "Default")
      (node (ref "30") (pin "1") (pinfunction "1_1") (pintype "passive"))
    )
    (net (code "87") (name "/SW2") (class "Default")
      (node (ref "R53") (pin "2") (pinfunction "2_2") (pintype "passive"))
      (node (ref "SW2") (pin "2") (pinfunction "2_2") (pintype "passive"))
      (node (ref "SW2") (pin "4") (pinfunction "4_4") (pintype "passive"))
    )
    (net (code "88") (name "/SW3") (class "Default")
      (node (ref "R54") (pin "2") (pinfunction "2_2") (pintype "passive"))
      (node (ref "SW3") (pin "2") (pinfunction "2_2") (pintype "passive"))
      (node (ref "SW3") (pin "4") (pinfunction "4_4") (pintype "passive"))
    )
    (net (code "89") (name "/SWCLK") (class "Default")
      (node (ref "6") (pin "1") (pinfunction "1_1") (pintype "passive"))
      (node (ref "H4") (pin "3") (pinfunction "3_3") (pintype "passive"))
    )
    (net (code "90") (name "/SWDIO") (class "Default")
      (node (ref "7") (pin "1") (pinfunction "1_1") (pintype "passive"))
      (node (ref "H4") (pin "1") (pinfunction "1_1") (pintype "passive"))
    )
    (net (code "91") (name "/SWD_EN") (class "Default")
      (node (ref "23") (pin "1") (pinfunction "1_1") (pintype "passive"))
    )
    (net (code "92") (name "/SWO") (class "Default")
      (node (ref "8") (pin "1") (pinfunction "1_1") (pintype "passive"))
      (node (ref "H4") (pin "4") (pinfunction "4_4") (pintype "passive"))
    )
    (net (code "93") (name "/SYSRST_N") (class "Default")
      (node (ref "5") (pin "1") (pinfunction "1_1") (pintype "passive"))
      (node (ref "C37") (pin "2") (pinfunction "2_2") (pintype "passive"))
      (node (ref "D11") (pin "1") (pinfunction "A1_1") (pintype "passive"))
      (node (ref "R8") (pin "2") (pinfunction "2_2") (pintype "passive"))
    )
    (net (code "94") (name "/TEST_IN") (class "Default")
      (node (ref "9") (pin "1") (pinfunction "1_1") (pintype "passive"))
    )
    (net (code "95") (name "/WAKEUP") (class "Default")
      (node (ref "1") (pin "1") (pinfunction "1_1") (pintype "passive"))
      (node (ref "D11") (pin "2") (pinfunction "A2_2") (pintype "passive"))
      (node (ref "H3") (pin "4") (pinfunction "4_4") (pintype "passive"))
    )
    (net (code "96") (name "3V3_AO") (class "Default")
      (node (ref "41") (pin "1") (pinfunction "1_1") (pintype "passive"))
      (node (ref "C28") (pin "2") (pinfunction "2_2") (pintype "passive"))
      (node (ref "C4") (pin "2") (pinfunction "2_2") (pintype "passive"))
      (node (ref "D1") (pin "4") (pinfunction "A_4") (pintype "passive"))
      (node (ref "D2") (pin "4") (pinfunction "A_4") (pintype "passive"))
      (node (ref "D3") (pin "4") (pinfunction "A_4") (pintype "passive"))
      (node (ref "D4") (pin "4") (pinfunction "A_4") (pintype "passive"))
      (node (ref "D5") (pin "4") (pinfunction "A_4") (pintype "passive"))
      (node (ref "D6") (pin "4") (pinfunction "A_4") (pintype "passive"))
      (node (ref "D9") (pin "1") (pinfunction "A1_1") (pintype "passive"))
      (node (ref "H3") (pin "3") (pinfunction "3_3") (pintype "passive"))
      (node (ref "L3") (pin "2") (pinfunction "2_2") (pintype "passive"))
      (node (ref "R33") (pin "1") (pinfunction "1_1") (pintype "passive"))
      (node (ref "R53") (pin "1") (pinfunction "1_1") (pintype "passive"))
      (node (ref "R54") (pin "1") (pinfunction "1_1") (pintype "passive"))
      (node (ref "R64") (pin "1") (pinfunction "1_1") (pintype "passive"))
    )
    (net (code "97") (name "3V3_MT") (class "Default")
      (node (ref "19") (pin "1") (pinfunction "1_1") (pintype "passive"))
      (node (ref "J2") (pin "2") (pinfunction "2_2") (pintype "passive"))
      (node (ref "R6") (pin "1") (pinfunction "1_1") (pintype "passive"))
      (node (ref "R8") (pin "1") (pinfunction "1_1") (pintype "passive"))
    )
    (net (code "98") (name "3V3_RTC") (class "Default")
      (node (ref "24") (pin "1") (pinfunction "1_1") (pintype "passive"))
      (node (ref "J3") (pin "2") (pinfunction "2_2") (pintype "passive"))
    )
    (net (code "99") (name "5V") (class "Default")
      (node (ref "C24") (pin "2") (pinfunction "2_2") (pintype "passive"))
      (node (ref "H3") (pin "1") (pinfunction "1_1") (pintype "passive"))
      (node (ref "J6") (pin "1") (pinfunction "1_1") (pintype "passive"))
      (node (ref "Q1") (pin "4") (pinfunction "D2_4") (pintype "passive"))
      (node (ref "Q2") (pin "2") (pinfunction "S_2") (pintype "passive"))
      (node (ref "Q3") (pin "4") (pinfunction "E2_4") (pintype "passive"))
      (node (ref "R60") (pin "1") (pinfunction "1_1") (pintype "passive"))
    )
    (net (code "100") (name "GND") (class "Default")
      (node (ref "21") (pin "1") (pinfunction "1_1") (pintype "passive"))
      (node (ref "36") (pin "1") (pinfunction "1_1") (pintype "passive"))
      (node (ref "37") (pin "1") (pinfunction "1_1") (pintype "passive"))
      (node (ref "38") (pin "1") (pinfunction "1_1") (pintype "passive"))
      (node (ref "B1") (pin "2") (pinfunction "-_2") (pintype "passive"))
      (node (ref "C24") (pin "1") (pinfunction "1_1") (pintype "passive"))
      (node (ref "C25") (pin "1") (pinfunction "1_1") (pintype "passive"))
      (node (ref "C27") (pin "1") (pinfunction "1_1") (pintype "passive"))
      (node (ref "C28") (pin "1") (pinfunction "1_1") (pintype "passive"))
      (node (ref "C37") (pin "1") (pinfunction "1_1") (pintype "passive"))
      (node (ref "C96") (pin "1") (pinfunction "1_1") (pintype "passive"))
      (node (ref "C97") (pin "1") (pinfunction "1_1") (pintype "passive"))
      (node (ref "D10") (pin "1") (pinfunction "K_1") (pintype "passive"))
      (node (ref "D7") (pin "1") (pinfunction "K_1") (pintype "passive"))
      (node (ref "GND") (pin "1") (pinfunction "1_1") (pintype "passive"))
      (node (ref "H1") (pin "2") (pinfunction "2_2") (pintype "passive"))
      (node (ref "H2") (pin "2") (pinfunction "2_2") (pintype "passive"))
      (node (ref "H3") (pin "2") (pinfunction "2_2") (pintype "passive"))
      (node (ref "H4") (pin "2") (pinfunction "2_2") (pintype "passive"))
      (node (ref "J6") (pin "2") (pinfunction "2_2") (pintype "passive"))
      (node (ref "R41") (pin "2") (pinfunction "2_2") (pintype "passive"))
      (node (ref "R5") (pin "2") (pinfunction "2_2") (pintype "passive"))
      (node (ref "R56") (pin "2") (pinfunction "2_2") (pintype "passive"))
      (node (ref "R57") (pin "2") (pinfunction "2_2") (pintype "passive"))
      (node (ref "R61") (pin "2") (pinfunction "2_2") (pintype "passive"))
      (node (ref "SW1") (pin "3") (pinfunction "3_3") (pintype "passive"))
      (node (ref "SW1") (pin "4") (pinfunction "4_4") (pintype "passive"))
      (node (ref "SW2") (pin "1") (pinfunction "1_1") (pintype "passive"))
      (node (ref "SW2") (pin "3") (pinfunction "3_3") (pintype "passive"))
      (node (ref "SW3") (pin "1") (pinfunction "1_1") (pintype "passive"))
      (node (ref "SW3") (pin "3") (pinfunction "3_3") (pintype "passive"))
      (node (ref "U19") (pin "2") (pinfunction "GND_2") (pintype "passive"))
      (node (ref "U8") (pin "1") (pinfunction "GND_1") (pintype "passive"))
      (node (ref "U8") (pin "4") (pinfunction "~{ON}_4") (pintype "passive"))
      (node (ref "U8") (pin "9") (pinfunction "EPAD_9") (pintype "passive"))
      (node (ref "U9") (pin "2") (pinfunction "GND_2") (pintype "passive"))
    )
    (net (code "101") (name "Net-(B1-+)") (class "Default")
      (node (ref "B1") (pin "1") (pinfunction "+_1") (pintype "passive"))
      (node (ref "R63") (pin "2") (pinfunction "2_2") (pintype "passive"))
    )
    (net (code "102") (name "Net-(C26-Pad2)") (class "Default")
      (node (ref "C26") (pin "2") (pinfunction "2_2") (pintype "passive"))
      (node (ref "C27") (pin "2") (pinfunction "2_2") (pintype "passive"))
      (node (ref "J2") (pin "1") (pinfunction "1_1") (pintype "passive"))
      (node (ref "L9") (pin "2") (pinfunction "2_2") (pintype "passive"))
      (node (ref "R4") (pin "1") (pinfunction "1_1") (pintype "passive"))
    )
    (net (code "103") (name "Net-(C95-Pad1)") (class "Default")
      (node (ref "C95") (pin "1") (pinfunction "1_1") (pintype "passive"))
      (node (ref "R61") (pin "1") (pinfunction "1_1") (pintype "passive"))
    )
    (net (code "104") (name "Net-(D1-B)") (class "Default")
      (node (ref "D1") (pin "3") (pinfunction "B_3") (pintype "passive"))
      (node (ref "RP3") (pin "1") (pinfunction "1_1") (pintype "passive"))
    )
    (net (code "105") (name "Net-(D1-G)") (class "Default")
      (node (ref "D1") (pin "2") (pinfunction "G_2") (pintype "passive"))
      (node (ref "RP2") (pin "1") (pinfunction "1_1") (pintype "passive"))
    )
    (net (code "106") (name "Net-(D1-R)") (class "Default")
      (node (ref "D1") (pin "1") (pinfunction "R_1") (pintype "passive"))
      (node (ref "RP1") (pin "1") (pinfunction "1_1") (pintype "passive"))
    )
    (net (code "107") (name "Net-(D2-B)") (class "Default")
      (node (ref "D2") (pin "3") (pinfunction "B_3") (pintype "passive"))
      (node (ref "RP3") (pin "3") (pinfunction "3_3") (pintype "passive"))
    )
    (net (code "108") (name "Net-(D2-G)") (class "Default")
      (node (ref "D2") (pin "2") (pinfunction "G_2") (pintype "passive"))
      (node (ref "RP2") (pin "3") (pinfunction "3_3") (pintype "passive"))
    )
    (net (code "109") (name "Net-(D2-R)") (class "Default")
      (node (ref "D2") (pin "1") (pinfunction "R_1") (pintype "passive"))
      (node (ref "RP1") (pin "3") (pinfunction "3_3") (pintype "passive"))
    )
    (net (code "110") (name "Net-(D3-B)") (class "Default")
      (node (ref "D3") (pin "3") (pinfunction "B_3") (pintype "passive"))
      (node (ref "RP3") (pin "5") (pinfunction "5_5") (pintype "passive"))
    )
    (net (code "111") (name "Net-(D3-G)") (class "Default")
      (node (ref "D3") (pin "2") (pinfunction "G_2") (pintype "passive"))
      (node (ref "RP2") (pin "5") (pinfunction "5_5") (pintype "passive"))
    )
    (net (code "112") (name "Net-(D3-R)") (class "Default")
      (node (ref "D3") (pin "1") (pinfunction "R_1") (pintype "passive"))
      (node (ref "RP1") (pin "5") (pinfunction "5_5") (pintype "passive"))
    )
    (net (code "113") (name "Net-(D4-B)") (class "Default")
      (node (ref "D4") (pin "3") (pinfunction "B_3") (pintype "passive"))
      (node (ref "RP3") (pin "7") (pinfunction "7_7") (pintype "passive"))
    )
    (net (code "114") (name "Net-(D4-G)") (class "Default")
      (node (ref "D4") (pin "2") (pinfunction "G_2") (pintype "passive"))
      (node (ref "RP2") (pin "7") (pinfunction "7_7") (pintype "passive"))
    )
    (net (code "115") (name "Net-(D4-R)") (class "Default")
      (node (ref "D4") (pin "1") (pinfunction "R_1") (pintype "passive"))
      (node (ref "RP1") (pin "7") (pinfunction "7_7") (pintype "passive"))
    )
    (net (code "116") (name "Net-(D5-B)") (class "Default")
      (node (ref "D5") (pin "3") (pinfunction "B_3") (pintype "passive"))
      (node (ref "R16") (pin "2") (pinfunction "2_2") (pintype "passive"))
    )
    (net (code "117") (name "Net-(D5-G)") (class "Default")
      (node (ref "D5") (pin "2") (pinfunction "G_2") (pintype "passive"))
      (node (ref "R15") (pin "1") (pinfunction "1_1") (pintype "passive"))
    )
    (net (code "118") (name "Net-(D5-R)") (class "Default")
      (node (ref "D5") (pin "1") (pinfunction "R_1") (pintype "passive"))
      (node (ref "R14") (pin "1") (pinfunction "1_1") (pintype "passive"))
    )
    (net (code "119") (name "Net-(D6-B)") (class "Default")
      (node (ref "D6") (pin "3") (pinfunction "B_3") (pintype "passive"))
      (node (ref "R19") (pin "2") (pinfunction "2_2") (pintype "passive"))
    )
    (net (code "120") (name "Net-(D6-G)") (class "Default")
      (node (ref "D6") (pin "2") (pinfunction "G_2") (pintype "passive"))
      (node (ref "R18") (pin "1") (pinfunction "1_1") (pintype "passive"))
    )
    (net (code "121") (name "Net-(D6-R)") (class "Default")
      (node (ref "D6") (pin "1") (pinfunction "R_1") (pintype "passive"))
      (node (ref "R17") (pin "1") (pinfunction "1_1") (pintype "passive"))
    )
    (net (code "122") (name "Net-(D7-A)") (class "Default")
      (node (ref "D7") (pin "2") (pinfunction "A_2") (pintype "passive"))
      (node (ref "R6") (pin "2") (pinfunction "2_2") (pintype "passive"))
    )
    (net (code "123") (name "Net-(D9A-K)") (class "Default")
      (node (ref "C97") (pin "2") (pinfunction "2_2") (pintype "passive"))
      (node (ref "D9") (pin "3") (pinfunction "K_3") (pintype "passive"))
      (node (ref "J3") (pin "1") (pinfunction "1_1") (pintype "passive"))
    )
    (net (code "124") (name "Net-(D9B-A2)") (class "Default")
      (node (ref "D9") (pin "2") (pinfunction "A2_2") (pintype "passive"))
      (node (ref "R63") (pin "1") (pinfunction "1_1") (pintype "passive"))
    )
    (net (code "125") (name "Net-(D10-A)") (class "Default")
      (node (ref "D10") (pin "2") (pinfunction "A_2") (pintype "passive"))
      (node (ref "R64") (pin "2") (pinfunction "2_2") (pintype "passive"))
    )
    (net (code "126") (name "Net-(H1-Pad1)") (class "Default")
      (node (ref "H1") (pin "1") (pinfunction "1_1") (pintype "passive"))
      (node (ref "R66") (pin "2") (pinfunction "2_2") (pintype "passive"))
    )
    (net (code "127") (name "Net-(J4-Pad2)") (class "Default")
      (node (ref "J4") (pin "2") (pinfunction "2_2") (pintype "passive"))
      (node (ref "R65") (pin "2") (pinfunction "2_2") (pintype "passive"))
    )
    (net (code "128") (name "Net-(Q1A-D1)") (class "Default")
      (node (ref "Q1") (pin "6") (pinfunction "D1_6") (pintype "passive"))
      (node (ref "R3") (pin "1") (pinfunction "1_1") (pintype "passive"))
      (node (ref "U8") (pin "7") (pinfunction "SENSE_7") (pintype "passive"))
    )
    (net (code "129") (name "Net-(Q1A-G1)") (class "Default")
      (node (ref "Q1") (pin "1") (pinfunction "G1_1") (pintype "passive"))
      (node (ref "U8") (pin "6") (pinfunction "GATE_6") (pintype "passive"))
    )
    (net (code "130") (name "Net-(Q1A-S1)") (class "Default")
      (node (ref "C25") (pin "2") (pinfunction "2_2") (pintype "passive"))
      (node (ref "Q1") (pin "5") (pinfunction "S1_5") (pintype "passive"))
      (node (ref "R40") (pin "1") (pinfunction "1_1") (pintype "passive"))
      (node (ref "U19") (pin "1") (pinfunction "EN_1") (pintype "passive"))
      (node (ref "U19") (pin "4") (pinfunction "VIN_4") (pintype "passive"))
      (node (ref "U8") (pin "3") (pinfunction "OUT_3") (pintype "passive"))
      (node (ref "U9") (pin "4") (pinfunction "VIN_4") (pintype "passive"))
    )
    (net (code "131") (name "Net-(Q1B-G2)") (class "Default")
      (node (ref "Q1") (pin "3") (pinfunction "G2_3") (pintype "passive"))
      (node (ref "U8") (pin "2") (pinfunction "GATEP_2") (pintype "passive"))
    )
    (net (code "132") (name "Net-(Q1B-S2)") (class "Default")
      (node (ref "Q1") (pin "2") (pinfunction "S2_2") (pintype "passive"))
      (node (ref "R3") (pin "2") (pinfunction "2_2") (pintype "passive"))
      (node (ref "U8") (pin "8") (pinfunction "IN_8") (pintype "passive"))
    )
    (net (code "133") (name "Net-(Q2-G)") (class "Default")
      (node (ref "Q2") (pin "1") (pinfunction "G_1") (pintype "passive"))
      (node (ref "Q3") (pin "3") (pinfunction "C2_3") (pintype "passive"))
      (node (ref "R57") (pin "1") (pinfunction "1_1") (pintype "passive"))
    )
    (net (code "134") (name "Net-(Q3A-B1)") (class "Default")
      (node (ref "Q3") (pin "2") (pinfunction "B1_2") (pintype "passive"))
      (node (ref "Q3") (pin "5") (pinfunction "B2_5") (pintype "passive"))
      (node (ref "Q3") (pin "6") (pinfunction "C1_6") (pintype "passive"))
      (node (ref "R56") (pin "1") (pinfunction "1_1") (pintype "passive"))
    )
    (net (code "135") (name "Net-(Q3A-E1)") (class "Default")
      (node (ref "C96") (pin "2") (pinfunction "2_2") (pintype "passive"))
      (node (ref "Q3") (pin "1") (pinfunction "E1_1") (pintype "passive"))
      (node (ref "R62") (pin "2") (pinfunction "2_2") (pintype "passive"))
    )
    (net (code "136") (name "Net-(U9-EN)") (class "Default")
      (node (ref "R40") (pin "2") (pinfunction "2_2") (pintype "passive"))
      (node (ref "R65") (pin "1") (pinfunction "1_1") (pintype "passive"))
      (node (ref "U9") (pin "1") (pinfunction "EN_1") (pintype "passive"))
    )
    (net (code "137") (name "Net-(U9-FB)") (class "Default")
      (node (ref "C26") (pin "1") (pinfunction "1_1") (pintype "passive"))
      (node (ref "R4") (pin "2") (pinfunction "2_2") (pintype "passive"))
      (node (ref "R5") (pin "1") (pinfunction "1_1") (pintype "passive"))
      (node (ref "U9") (pin "5") (pinfunction "FB_5") (pintype "passive"))
    )
    (net (code "138") (name "Net-(U9-SW)") (class "Default")
      (node (ref "L9") (pin "1") (pinfunction "1_1") (pintype "passive"))
      (node (ref "U9") (pin "3") (pinfunction "SW_3") (pintype "passive"))
    )
    (net (code "139") (name "Net-(U19-FB)") (class "Default")
      (node (ref "C4") (pin "1") (pinfunction "1_1") (pintype "passive"))
      (node (ref "R33") (pin "2") (pinfunction "2_2") (pintype "passive"))
      (node (ref "R41") (pin "1") (pinfunction "1_1") (pintype "passive"))
      (node (ref "U19") (pin "5") (pinfunction "FB_5") (pintype "passive"))
    )
    (net (code "140") (name "Net-(U19-SW)") (class "Default")
      (node (ref "L3") (pin "1") (pinfunction "1_1") (pintype "passive"))
      (node (ref "U19") (pin "3") (pinfunction "SW_3") (pintype "passive"))
    )
    (net (code "141") (name "VBUS") (class "Default")
      (node (ref "20") (pin "1") (pinfunction "1_1") (pintype "passive"))
      (node (ref "C95") (pin "2") (pinfunction "2_2") (pintype "passive"))
      (node (ref "Q2") (pin "3") (pinfunction "D_3") (pintype "passive"))
      (node (ref "R60") (pin "2") (pinfunction "2_2") (pintype "passive"))
      (node (ref "R62") (pin "1") (pinfunction "1_1") (pintype "passive"))
    )
    (net (code "142") (name "unconnected-(J6-Pad3)") (class "Default")
      (node (ref "J6") (pin "3") (pinfunction "3_3") (pintype "passive"))
    )
    (net (code "143") (name "unconnected-(U8-~{PWRGD}-Pad5)") (class "Default")
      (node (ref "U8") (pin "5") (pinfunction "~{PWRGD}_5") (pintype "passive+no_connect"))
    )
  )
)
